# Parte_digital.net
KiCad netlist of a schematic drawn in Altium Designer
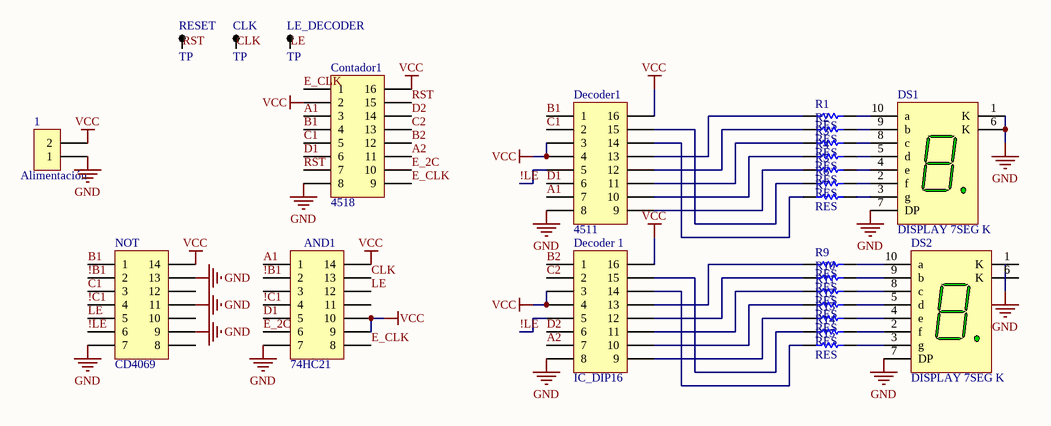
[diagram p0: Parte_digital.SchDoc]

(export (version "E")
  (design (tool "Eeschema 10.0.6"))
  (components
    (comp (ref "1")
      (value "Alimentación")
      (footprint "BORNERA2")
      (libsource (lib "LIBEBAL") (part "BORNERA 2"))
    )
    (comp (ref "AND1") (value "74HC21") (footprint "DIP14") (libsource (lib "LIBEBAL") (part "IC_DIP14")))
    (comp (ref "CLK") (value "TP") (footprint "TPTH") (libsource (lib "LIBEBAL") (part "TP")))
    (comp (ref "Contador1") (value "4518") (footprint "DIP16") (libsource (lib "LIBEBAL") (part "IC_DIP16")))
    (comp (ref "Decoder 1")
      (value "IC_DIP16")
      (footprint "DIP16")
      (libsource (lib "LIBEBAL") (part "IC_DIP16"))
    )
    (comp (ref "Decoder1") (value "4511") (footprint "DIP16") (libsource (lib "LIBEBAL") (part "IC_DIP16")))
    (comp (ref "DS1")
      (value "DISPLAY 7SEG K")
      (footprint "DISPLAY_LED_0.3\"")
      (description "Display 7 Segmentos Catodo Común")
      (libsource (lib "LIBEBAL") (part "DISPLAY 7SEG K"))
    )
    (comp (ref "DS2")
      (value "DISPLAY 7SEG K")
      (footprint "DISPLAY_LED_0.3\"")
      (description "Display 7 Segmentos Catodo Común")
      (libsource (lib "LIBEBAL") (part "DISPLAY 7SEG K"))
    )
    (comp (ref "LE_DECODER") (value "TP") (footprint "TPTH") (libsource (lib "LIBEBAL") (part "TP")))
    (comp (ref "NOT") (value "CD4069") (footprint "DIP14") (libsource (lib "LIBEBAL") (part "IC_DIP14")))
    (comp (ref "R1") (value "RES") (footprint "RES400") (libsource (lib "LIBEBAL") (part "RES")))
    (comp (ref "R2") (value "RES") (footprint "RES400") (libsource (lib "LIBEBAL") (part "RES")))
    (comp (ref "R3") (value "RES") (footprint "RES400") (libsource (lib "LIBEBAL") (part "RES")))
    (comp (ref "R4") (value "RES") (footprint "RES400") (libsource (lib "LIBEBAL") (part "RES")))
    (comp (ref "R5") (value "RES") (footprint "RES400") (libsource (lib "LIBEBAL") (part "RES")))
    (comp (ref "R6") (value "RES") (footprint "RES400") (libsource (lib "LIBEBAL") (part "RES")))
    (comp (ref "R7") (value "RES") (footprint "RES400") (libsource (lib "LIBEBAL") (part "RES")))
    (comp (ref "R9") (value "RES") (footprint "RES400") (libsource (lib "LIBEBAL") (part "RES")))
    (comp (ref "R10") (value "RES") (footprint "RES400") (libsource (lib "LIBEBAL") (part "RES")))
    (comp (ref "R11") (value "RES") (footprint "RES400") (libsource (lib "LIBEBAL") (part "RES")))
    (comp (ref "R12") (value "RES") (footprint "RES400") (libsource (lib "LIBEBAL") (part "RES")))
    (comp (ref "R13") (value "RES") (footprint "RES400") (libsource (lib "LIBEBAL") (part "RES")))
    (comp (ref "R14") (value "RES") (footprint "RES400") (libsource (lib "LIBEBAL") (part "RES")))
    (comp (ref "R15") (value "RES") (footprint "RES400") (libsource (lib "LIBEBAL") (part "RES")))
    (comp (ref "RESET") (value "TP") (footprint "TPTH") (libsource (lib "LIBEBAL") (part "TP")))
  )
  (nets
    (net (code "1") (name "/!B1") (class "Default")
      (node (ref "AND1") (pin "2") (pinfunction "2_2") (pintype "passive"))
      (node (ref "NOT") (pin "2") (pinfunction "2_2") (pintype "passive"))
    )
    (net (code "2") (name "/!C1") (class "Default")
      (node (ref "AND1") (pin "4") (pinfunction "4_4") (pintype "passive"))
      (node (ref "NOT") (pin "4") (pinfunction "4_4") (pintype "passive"))
    )
    (net (code "3") (name "/!LE") (class "Default")
      (node (ref "Decoder 1") (pin "5") (pinfunction "5_5") (pintype "passive"))
      (node (ref "Decoder1") (pin "5") (pinfunction "5_5") (pintype "passive"))
      (node (ref "NOT") (pin "6") (pinfunction "6_6") (pintype "passive"))
    )
    (net (code "4") (name "/A1") (class "Default")
      (node (ref "AND1") (pin "1") (pinfunction "1_1") (pintype "passive"))
      (node (ref "Contador1") (pin "3") (pinfunction "3_3") (pintype "passive"))
      (node (ref "Decoder1") (pin "7") (pinfunction "7_7") (pintype "passive"))
    )
    (net (code "5") (name "/A2") (class "Default")
      (node (ref "Contador1") (pin "11") (pinfunction "11_11") (pintype "passive"))
      (node (ref "Decoder 1") (pin "7") (pinfunction "7_7") (pintype "passive"))
    )
    (net (code "6") (name "/B1") (class "Default")
      (node (ref "Contador1") (pin "4") (pinfunction "4_4") (pintype "passive"))
      (node (ref "Decoder1") (pin "1") (pinfunction "1_1") (pintype "passive"))
      (node (ref "NOT") (pin "1") (pinfunction "1_1") (pintype "passive"))
    )
    (net (code "7") (name "/B2") (class "Default")
      (node (ref "Contador1") (pin "12") (pinfunction "12_12") (pintype "passive"))
      (node (ref "Decoder 1") (pin "1") (pinfunction "1_1") (pintype "passive"))
    )
    (net (code "8") (name "/C1") (class "Default")
      (node (ref "Contador1") (pin "5") (pinfunction "5_5") (pintype "passive"))
      (node (ref "Decoder1") (pin "2") (pinfunction "2_2") (pintype "passive"))
      (node (ref "NOT") (pin "3") (pinfunction "3_3") (pintype "passive"))
    )
    (net (code "9") (name "/C2") (class "Default")
      (node (ref "Contador1") (pin "13") (pinfunction "13_13") (pintype "passive"))
      (node (ref "Decoder 1") (pin "2") (pinfunction "2_2") (pintype "passive"))
    )
    (net (code "10") (name "/CLK") (class "Default")
      (node (ref "AND1") (pin "13") (pinfunction "13_13") (pintype "passive"))
      (node (ref "CLK") (pin "1") (pinfunction "1_1") (pintype "passive"))
    )
    (net (code "11") (name "/D1") (class "Default")
      (node (ref "AND1") (pin "5") (pinfunction "5_5") (pintype "passive"))
      (node (ref "Contador1") (pin "6") (pinfunction "6_6") (pintype "passive"))
      (node (ref "Decoder1") (pin "6") (pinfunction "6_6") (pintype "passive"))
    )
    (net (code "12") (name "/D2") (class "Default")
      (node (ref "Contador1") (pin "14") (pinfunction "14_14") (pintype "passive"))
      (node (ref "Decoder 1") (pin "6") (pinfunction "6_6") (pintype "passive"))
    )
    (net (code "13") (name "/E_2C") (class "Default")
      (node (ref "AND1") (pin "6") (pinfunction "6_6") (pintype "passive"))
      (node (ref "Contador1") (pin "10") (pinfunction "10_10") (pintype "passive"))
    )
    (net (code "14") (name "/E_CLK") (class "Default")
      (node (ref "AND1") (pin "8") (pinfunction "8_8") (pintype "passive"))
      (node (ref "Contador1") (pin "1") (pinfunction "1_1") (pintype "passive"))
      (node (ref "Contador1") (pin "9") (pinfunction "9_9") (pintype "passive"))
    )
    (net (code "15") (name "/LE") (class "Default")
      (node (ref "AND1") (pin "12") (pinfunction "12_12") (pintype "passive"))
      (node (ref "LE_DECODER") (pin "1") (pinfunction "1_1") (pintype "passive"))
      (node (ref "NOT") (pin "5") (pinfunction "5_5") (pintype "passive"))
    )
    (net (code "16") (name "/RST") (class "Default")
      (node (ref "Contador1") (pin "15") (pinfunction "15_15") (pintype "passive"))
      (node (ref "Contador1") (pin "7") (pinfunction "7_7") (pintype "passive"))
      (node (ref "RESET") (pin "1") (pinfunction "1_1") (pintype "passive"))
    )
    (net (code "17") (name "GND") (class "Default")
      (node (ref "1") (pin "1") (pinfunction "1_1") (pintype "passive"))
      (node (ref "AND1") (pin "7") (pinfunction "7_7") (pintype "passive"))
      (node (ref "Contador1") (pin "8") (pinfunction "8_8") (pintype "passive"))
      (node (ref "DS1") (pin "1") (pinfunction "K_1") (pintype "passive"))
      (node (ref "DS1") (pin "6") (pinfunction "K_6") (pintype "passive"))
      (node (ref "DS1") (pin "7") (pinfunction "DP_7") (pintype "passive"))
      (node (ref "DS2") (pin "7") (pinfunction "DP_7") (pintype "passive"))
      (node (ref "Decoder 1") (pin "8") (pinfunction "8_8") (pintype "passive"))
      (node (ref "Decoder1") (pin "8") (pinfunction "8_8") (pintype "passive"))
      (node (ref "NOT") (pin "11") (pinfunction "11_11") (pintype "passive"))
      (node (ref "NOT") (pin "13") (pinfunction "13_13") (pintype "passive"))
      (node (ref "NOT") (pin "7") (pinfunction "7_7") (pintype "passive"))
      (node (ref "NOT") (pin "9") (pinfunction "9_9") (pintype "passive"))
    )
    (net (code "18") (name "Net-(DS1-a)") (class "Default")
      (node (ref "DS1") (pin "10") (pinfunction "a_10") (pintype "passive"))
      (node (ref "R1") (pin "2") (pinfunction "2_2") (pintype "passive"))
    )
    (net (code "19") (name "Net-(DS1-b)") (class "Default")
      (node (ref "DS1") (pin "9") (pinfunction "b_9") (pintype "passive"))
      (node (ref "R2") (pin "2") (pinfunction "2_2") (pintype "passive"))
    )
    (net (code "20") (name "Net-(DS1-c)") (class "Default")
      (node (ref "DS1") (pin "8") (pinfunction "c_8") (pintype "passive"))
      (node (ref "R3") (pin "2") (pinfunction "2_2") (pintype "passive"))
    )
    (net (code "21") (name "Net-(DS1-d)") (class "Default")
      (node (ref "DS1") (pin "5") (pinfunction "d_5") (pintype "passive"))
      (node (ref "R4") (pin "2") (pinfunction "2_2") (pintype "passive"))
    )
    (net (code "22") (name "Net-(DS1-e)") (class "Default")
      (node (ref "DS1") (pin "4") (pinfunction "e_4") (pintype "passive"))
      (node (ref "R5") (pin "2") (pinfunction "2_2") (pintype "passive"))
    )
    (net (code "23") (name "Net-(DS1-f)") (class "Default")
      (node (ref "DS1") (pin "2") (pinfunction "f_2") (pintype "passive"))
      (node (ref "R6") (pin "2") (pinfunction "2_2") (pintype "passive"))
    )
    (net (code "24") (name "Net-(DS1-g)") (class "Default")
      (node (ref "DS1") (pin "3") (pinfunction "g_3") (pintype "passive"))
      (node (ref "R7") (pin "2") (pinfunction "2_2") (pintype "passive"))
    )
    (net (code "25") (name "Net-(DS2-a)") (class "Default")
      (node (ref "DS2") (pin "10") (pinfunction "a_10") (pintype "passive"))
      (node (ref "R9") (pin "2") (pinfunction "2_2") (pintype "passive"))
    )
    (net (code "26") (name "Net-(DS2-b)") (class "Default")
      (node (ref "DS2") (pin "9") (pinfunction "b_9") (pintype "passive"))
      (node (ref "R10") (pin "2") (pinfunction "2_2") (pintype "passive"))
    )
    (net (code "27") (name "Net-(DS2-c)") (class "Default")
      (node (ref "DS2") (pin "8") (pinfunction "c_8") (pintype "passive"))
      (node (ref "R11") (pin "2") (pinfunction "2_2") (pintype "passive"))
    )
    (net (code "28") (name "Net-(DS2-d)") (class "Default")
      (node (ref "DS2") (pin "5") (pinfunction "d_5") (pintype "passive"))
      (node (ref "R12") (pin "2") (pinfunction "2_2") (pintype "passive"))
    )
    (net (code "29") (name "Net-(DS2-e)") (class "Default")
      (node (ref "DS2") (pin "4") (pinfunction "e_4") (pintype "passive"))
      (node (ref "R13") (pin "2") (pinfunction "2_2") (pintype "passive"))
    )
    (net (code "30") (name "Net-(DS2-f)") (class "Default")
      (node (ref "DS2") (pin "2") (pinfunction "f_2") (pintype "passive"))
      (node (ref "R14") (pin "2") (pinfunction "2_2") (pintype "passive"))
    )
    (net (code "31") (name "Net-(DS2-g)") (class "Default")
      (node (ref "DS2") (pin "3") (pinfunction "g_3") (pintype "passive"))
      (node (ref "R15") (pin "2") (pinfunction "2_2") (pintype "passive"))
    )
    (net (code "32") (name "Net-(Decoder 1-Pad9)") (class "Default")
      (node (ref "Decoder 1") (pin "9") (pinfunction "9_9") (pintype "passive"))
      (node (ref "R13") (pin "1") (pinfunction "1_1") (pintype "passive"))
    )
    (net (code "33") (name "Net-(Decoder 1-Pad10)") (class "Default")
      (node (ref "Decoder 1") (pin "10") (pinfunction "10_10") (pintype "passive"))
      (node (ref "R12") (pin "1") (pinfunction "1_1") (pintype "passive"))
    )
    (net (code "34") (name "Net-(Decoder 1-Pad11)") (class "Default")
      (node (ref "Decoder 1") (pin "11") (pinfunction "11_11") (pintype "passive"))
      (node (ref "R11") (pin "1") (pinfunction "1_1") (pintype "passive"))
    )
    (net (code "35") (name "Net-(Decoder 1-Pad12)") (class "Default")
      (node (ref "Decoder 1") (pin "12") (pinfunction "12_12") (pintype "passive"))
      (node (ref "R10") (pin "1") (pinfunction "1_1") (pintype "passive"))
    )
    (net (code "36") (name "Net-(Decoder 1-Pad13)") (class "Default")
      (node (ref "Decoder 1") (pin "13") (pinfunction "13_13") (pintype "passive"))
      (node (ref "R9") (pin "1") (pinfunction "1_1") (pintype "passive"))
    )
    (net (code "37") (name "Net-(Decoder 1-Pad14)") (class "Default")
      (node (ref "Decoder 1") (pin "14") (pinfunction "14_14") (pintype "passive"))
      (node (ref "R15") (pin "1") (pinfunction "1_1") (pintype "passive"))
    )
    (net (code "38") (name "Net-(Decoder 1-Pad15)") (class "Default")
      (node (ref "Decoder 1") (pin "15") (pinfunction "15_15") (pintype "passive"))
      (node (ref "R14") (pin "1") (pinfunction "1_1") (pintype "passive"))
    )
    (net (code "39") (name "Net-(Decoder1-Pad9)") (class "Default")
      (node (ref "Decoder1") (pin "9") (pinfunction "9_9") (pintype "passive"))
      (node (ref "R5") (pin "1") (pinfunction "1_1") (pintype "passive"))
    )
    (net (code "40") (name "Net-(Decoder1-Pad10)") (class "Default")
      (node (ref "Decoder1") (pin "10") (pinfunction "10_10") (pintype "passive"))
      (node (ref "R4") (pin "1") (pinfunction "1_1") (pintype "passive"))
    )
    (net (code "41") (name "Net-(Decoder1-Pad11)") (class "Default")
      (node (ref "Decoder1") (pin "11") (pinfunction "11_11") (pintype "passive"))
      (node (ref "R3") (pin "1") (pinfunction "1_1") (pintype "passive"))
    )
    (net (code "42") (name "Net-(Decoder1-Pad12)") (class "Default")
      (node (ref "Decoder1") (pin "12") (pinfunction "12_12") (pintype "passive"))
      (node (ref "R2") (pin "1") (pinfunction "1_1") (pintype "passive"))
    )
    (net (code "43") (name "Net-(Decoder1-Pad13)") (class "Default")
      (node (ref "Decoder1") (pin "13") (pinfunction "13_13") (pintype "passive"))
      (node (ref "R1") (pin "1") (pinfunction "1_1") (pintype "passive"))
    )
    (net (code "44") (name "Net-(Decoder1-Pad14)") (class "Default")
      (node (ref "Decoder1") (pin "14") (pinfunction "14_14") (pintype "passive"))
      (node (ref "R7") (pin "1") (pinfunction "1_1") (pintype "passive"))
    )
    (net (code "45") (name "Net-(Decoder1-Pad15)") (class "Default")
      (node (ref "Decoder1") (pin "15") (pinfunction "15_15") (pintype "passive"))
      (node (ref "R6") (pin "1") (pinfunction "1_1") (pintype "passive"))
    )
    (net (code "46") (name "VCC") (class "Default")
      (node (ref "1") (pin "2") (pinfunction "2_2") (pintype "passive"))
      (node (ref "AND1") (pin "10") (pinfunction "10_10") (pintype "passive"))
      (node (ref "AND1") (pin "14") (pinfunction "14_14") (pintype "passive"))
      (node (ref "AND1") (pin "9") (pinfunction "9_9") (pintype "passive"))
      (node (ref "Contador1") (pin "16") (pinfunction "16_16") (pintype "passive"))
      (node (ref "Contador1") (pin "2") (pinfunction "2_2") (pintype "passive"))
      (node (ref "Decoder 1") (pin "16") (pinfunction "16_16") (pintype "passive"))
      (node (ref "Decoder 1") (pin "3") (pinfunction "3_3") (pintype "passive"))
      (node (ref "Decoder 1") (pin "4") (pinfunction "4_4") (pintype "passive"))
      (node (ref "Decoder1") (pin "16") (pinfunction "16_16") (pintype "passive"))
      (node (ref "Decoder1") (pin "3") (pinfunction "3_3") (pintype "passive"))
      (node (ref "Decoder1") (pin "4") (pinfunction "4_4") (pintype "passive"))
      (node (ref "NOT") (pin "14") (pinfunction "14_14") (pintype "passive"))
    )
    (net (code "47") (name "unconnected-(AND1-Pad3)") (class "Default")
      (node (ref "AND1") (pin "3") (pinfunction "3_3") (pintype "passive"))
    )
    (net (code "48") (name "unconnected-(AND1-Pad11)") (class "Default")
      (node (ref "AND1") (pin "11") (pinfunction "11_11") (pintype "passive"))
    )
    (net (code "49") (name "unconnected-(DS2-K-Pad1)") (class "Default")
      (node (ref "DS2") (pin "1") (pinfunction "K_1") (pintype "passive"))
    )
    (net (code "50") (name "unconnected-(DS2-K-Pad6)") (class "Default")
      (node (ref "DS2") (pin "6") (pinfunction "K_6") (pintype "passive"))
    )
    (net (code "51") (name "unconnected-(NOT-Pad8)") (class "Default")
      (node (ref "NOT") (pin "8") (pinfunction "8_8") (pintype "passive"))
    )
    (net (code "52") (name "unconnected-(NOT-Pad10)") (class "Default")
      (node (ref "NOT") (pin "10") (pinfunction "10_10") (pintype "passive"))
    )
    (net (code "53") (name "unconnected-(NOT-Pad12)") (class "Default")
      (node (ref "NOT") (pin "12") (pinfunction "12_12") (pintype "passive"))
    )
  )
)
